# SAMD20_Xplained_Pro_dual_input_power_sup.net
KiCad netlist of a schematic drawn in Altium Designer
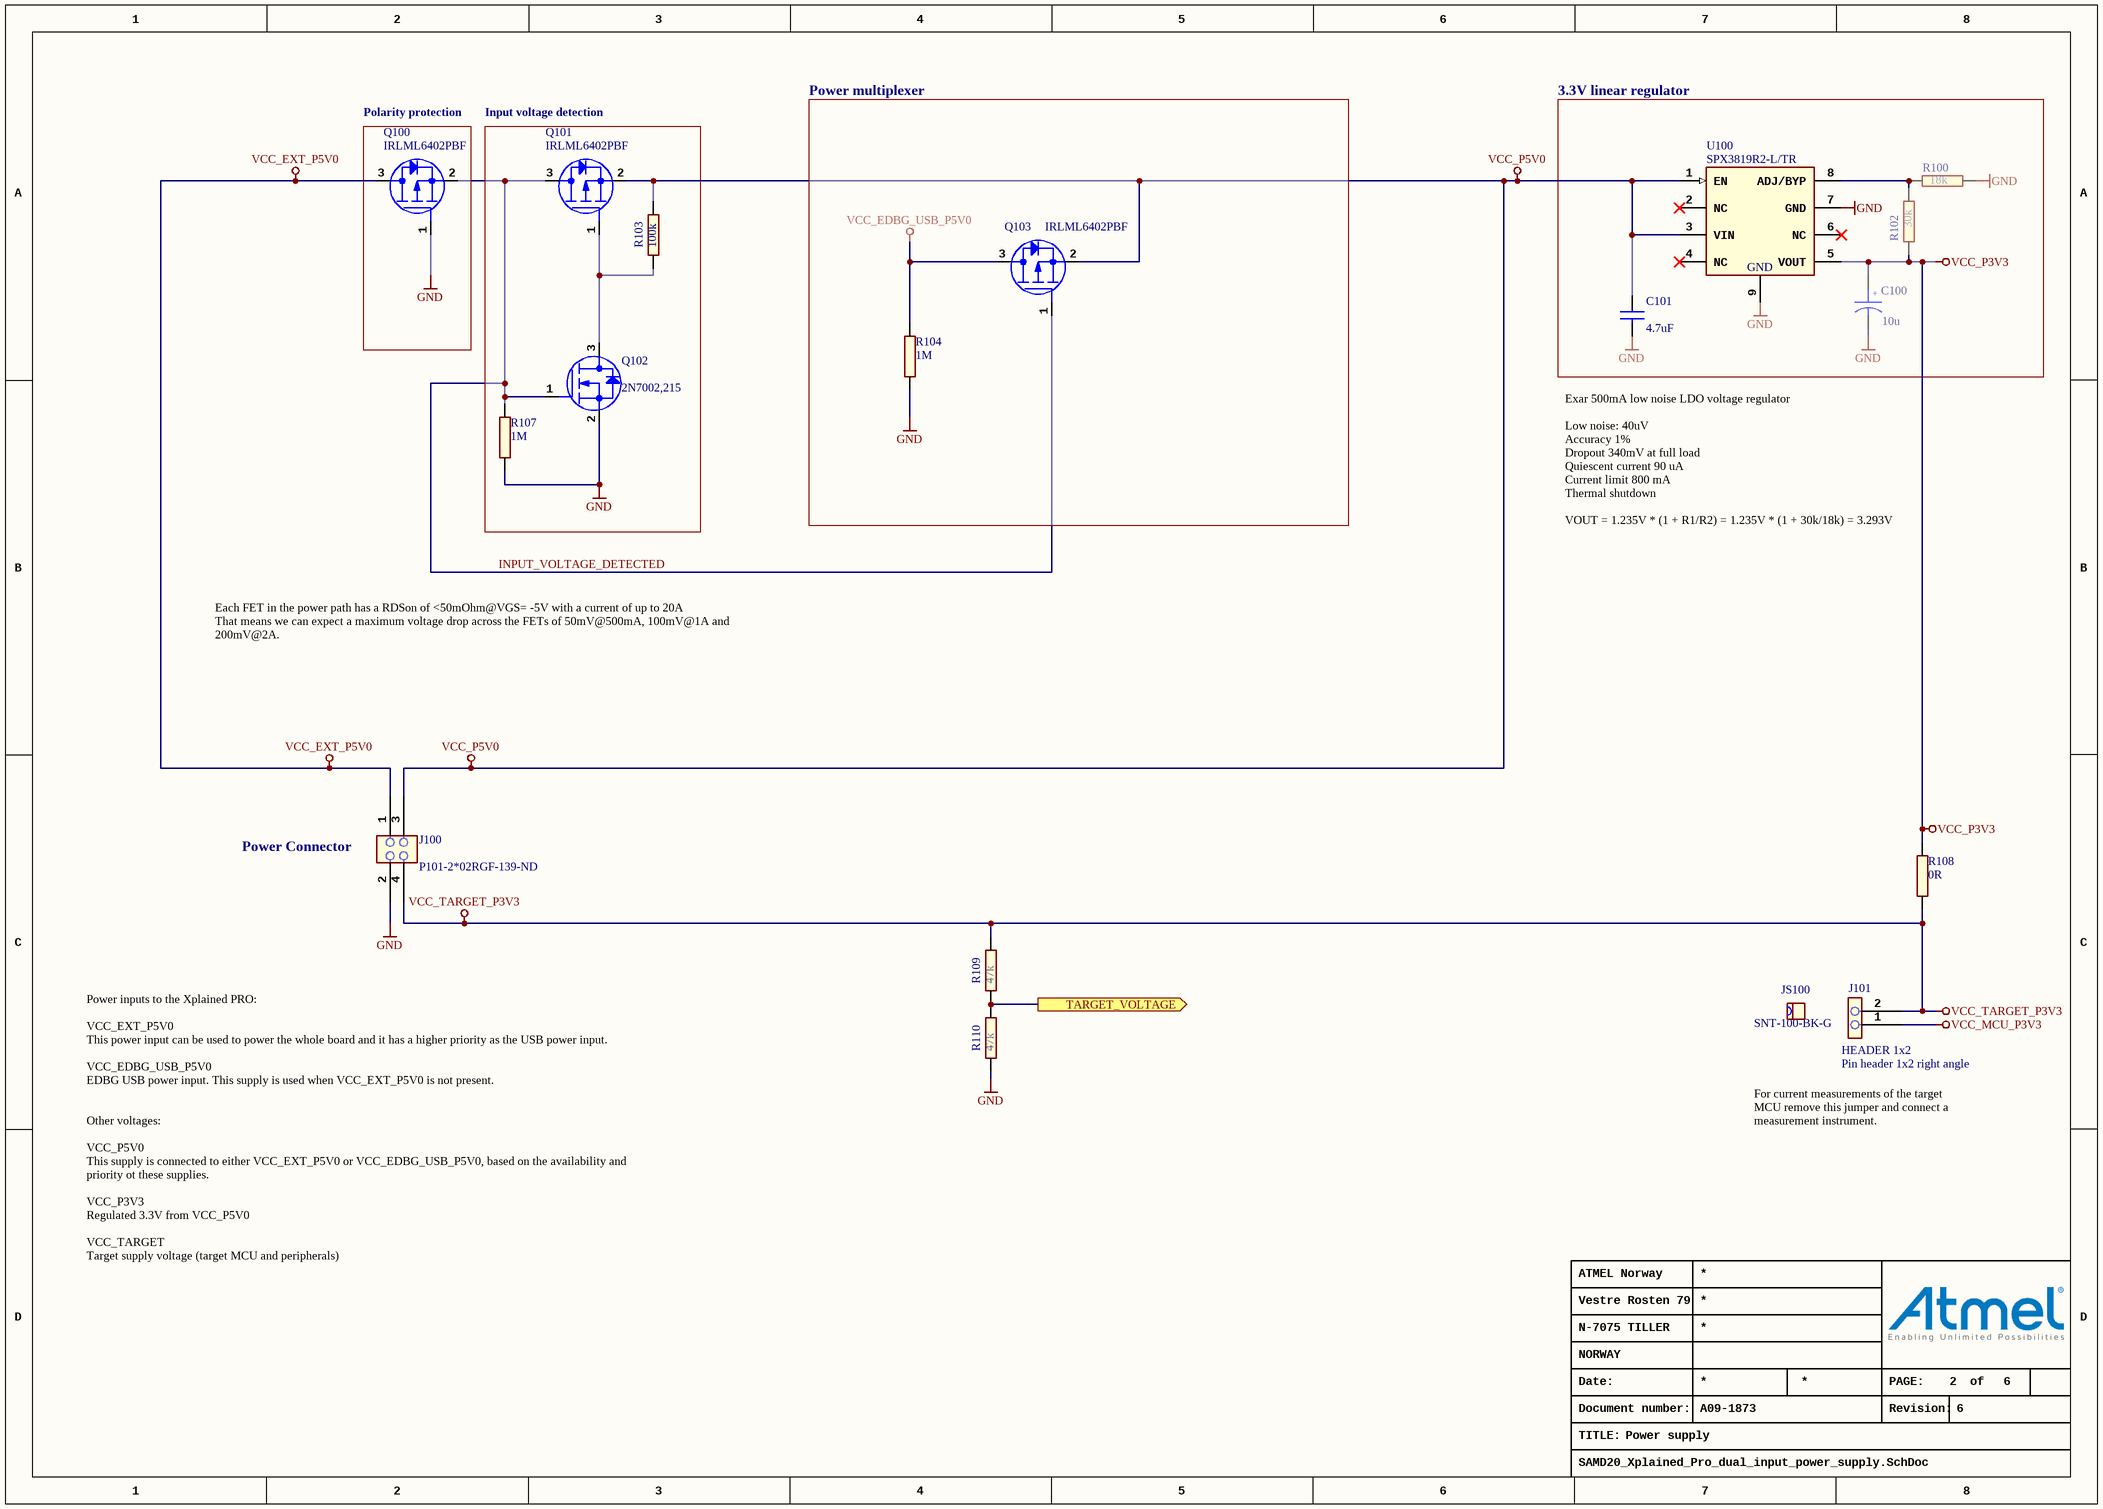
[diagram p0: SAMD20_Xplained_Pro_dual_input_power_supply.SchDoc]

(export (version "E")
  (design (tool "Eeschema 10.0.6"))
  (components
    (comp (ref "C100")
      (value "10u")
      (footprint "AP1-00036")
      (description "SMD tantalum capacitor, ESR = 1.7, 3216-18 (EIA) 1206,")
      (fields (field (name "TOLERANCE") "+-10%") (field (name "MANUFACTURER") "vishay"))
      (libsource (lib "AltiumDbLib") (part "CAP-POL"))
    )
    (comp (ref "C101")
      (value "4.7uF")
      (footprint "AP1-00039")
      (description "Ceramic capacitor, SMD 0603, X5R, 10V, 10% (de31036)")
      (fields (field (name "TOLERANCE") "10%") (field (name "MANUFACTURER") "tdk"))
      (libsource (lib "AltiumDbLib") (part "CAP-NONPOL"))
    )
    (comp (ref "J100")
      (value "P101-2*02RGF-139-ND")
      (footprint "AP8-00628")
      (description "Pin header, 2x2, Right Angle, 2.54mm, THT, Pin In Paste")
      (fields (field (name "Comment") "HEADER 2x2"))
      (libsource (lib "AltiumDbLib") (part "HEADER 2x2"))
    )
    (comp (ref "J101")
      (value "HEADER 1x2")
      (footprint "AP8-00367")
      (description "1x2 pin header, right angle, 2.54 mm pitch, through-hole")
      (fields
        (field (name "ALTIUM_VALUE") "Pin header 1x2 right angle")
        (field (name "MANUFACTURER") "Pro-data International Corp")
        (field (name "MPN") "2213R-2G")
      )
      (libsource (lib "AltiumDbLib") (part "HEADER 1x2"))
    )
    (comp (ref "JS100")
      (value "SNT-100-BK-G")
      (footprint "AP8-00525")
      (description "Jumper cap for 2.54mm pinheader")
      (fields (field (name "MANUFACTURER") "SAMTEC"))
      (libsource (lib "AltiumDbLib") (part "JUMPER_CAP"))
    )
    (comp (ref "Q100")
      (value "IRLML6402PBF")
      (footprint "AP5-00002")
      (description "P-ch. MOSFET. -30V, -3.7A continuous,RDS(ON)=0.05Ohm@VGS=-4,5V, RDS(ON)=0.08Ohm@VGS=-2.5V")
      (fields (field (name "MANUFACTURER") "International Rectifier") (field (name "Comment") "MOSFET_P_GSD"))
      (libsource (lib "AltiumDbLib") (part "MOSFET_P_GSD"))
    )
    (comp (ref "Q101")
      (value "IRLML6402PBF")
      (footprint "AP5-00002")
      (description "P-ch. MOSFET. -30V, -3.7A continuous,RDS(ON)=0.05Ohm@VGS=-4,5V, RDS(ON)=0.08Ohm@VGS=-2.5V")
      (fields (field (name "MANUFACTURER") "International Rectifier") (field (name "Comment") "MOSFET_P_GSD"))
      (libsource (lib "AltiumDbLib") (part "MOSFET_P_GSD"))
    )
    (comp (ref "Q102")
      (value "2N7002,215")
      (footprint "AP5-00002")
      (description "N-Channel MOSFET. 60V, 0.300A continuous, 1.2A Peak. RDS(ON) = 3.8Ohm@VGS=4.5V, VGS(th)<2.5V")
      (fields (field (name "MANUFACTURER") "NXP") (field (name "Comment") "MOSFET_N_GSD"))
      (libsource (lib "AltiumDbLib") (part "MOSFET_N_GSD"))
    )
    (comp (ref "Q103")
      (value "IRLML6402PBF")
      (footprint "AP5-00002")
      (description "P-ch. MOSFET. -30V, -3.7A continuous,RDS(ON)=0.05Ohm@VGS=-4,5V, RDS(ON)=0.08Ohm@VGS=-2.5V")
      (fields (field (name "MANUFACTURER") "International Rectifier") (field (name "Comment") "MOSFET_P_GSD"))
      (libsource (lib "AltiumDbLib") (part "MOSFET_P_GSD"))
    )
    (comp (ref "R100")
      (value "18k")
      (footprint "AP2-00000")
      (description "Thick film resistor, SMD 0402, 1/16W, 1%")
      (fields (field (name "TOLERANCE") "1 %") (field (name "Comment") "R2"))
      (libsource (lib "") (part "R2_3"))
    )
    (comp (ref "R102")
      (value "30k")
      (footprint "AP2-00000")
      (description "Thick film resistor, SMD 0402, 1/16W, 1%")
      (fields (field (name "TOLERANCE") "1 %") (field (name "Comment") "R2"))
      (libsource (lib "") (part "R2_2"))
    )
    (comp (ref "R103")
      (value "100k")
      (footprint "AP2-00000")
      (description "Thick film resistor, SMD 0402, 1/16W, 1%")
      (fields (field (name "TOLERANCE") "1 %") (field (name "Comment") "R2"))
      (libsource (lib "") (part "R2_2"))
    )
    (comp (ref "R104")
      (value "1M")
      (footprint "AP2-00000")
      (description "Thick film resistor, SMD 0402, 1/16W, 1%")
      (fields (field (name "TOLERANCE") "1 %") (field (name "MANUFACTURER") "KOA"))
      (libsource (lib "") (part "R2_2"))
    )
    (comp (ref "R107")
      (value "1M")
      (footprint "AP2-00000")
      (description "Thick film resistor, SMD 0402, 1/16W, 1%")
      (fields (field (name "TOLERANCE") "1 %") (field (name "Comment") "R2"))
      (libsource (lib "") (part "R2_2"))
    )
    (comp (ref "R108")
      (value "0R")
      (footprint "AP2-00000")
      (description "Thick film resistor, SMD 0402, 1/16W, 1%")
      (fields (field (name "TOLERANCE") "1 %") (field (name "Comment") "R2"))
      (libsource (lib "") (part "R2_1"))
    )
    (comp (ref "R109")
      (value "47k")
      (footprint "AP2-00000")
      (description "Thick film resistor, SMD 0402, 1/16W, 1%")
      (fields (field (name "TOLERANCE") "1 %") (field (name "Comment") "R2"))
      (libsource (lib "AltiumDbLib") (part "R2"))
    )
    (comp (ref "R110")
      (value "47k")
      (footprint "AP2-00000")
      (description "Thick film resistor, SMD 0402, 1/16W, 1%")
      (fields (field (name "TOLERANCE") "1 %") (field (name "Comment") "R2"))
      (libsource (lib "AltiumDbLib") (part "R2"))
    )
    (comp (ref "U100")
      (value "SPX3819R2-L/TR")
      (footprint "AP6-00338")
      (description "500mA LDO, ADJ, low noise, 8-DFN package")
      (fields (field (name "TOLERANCE") "±1%") (field (name "MANUFACTURER") "Exar"))
      (libsource (lib "AltiumDbLib") (part "SPX3819R2-L"))
    )
  )
  (nets
    (net (code "1") (name "/INPUT_VOLTAGE_DETECTED") (class "Default")
      (node (ref "Q100") (pin "2") (pinfunction "S_2") (pintype "passive"))
      (node (ref "Q101") (pin "3") (pinfunction "D_3") (pintype "passive"))
      (node (ref "Q102") (pin "1") (pinfunction "G_1") (pintype "passive"))
      (node (ref "Q103") (pin "1") (pinfunction "G_1") (pintype "passive"))
      (node (ref "R107") (pin "2") (pinfunction "2_2") (pintype "passive"))
    )
    (net (code "2") (name "/TARGET_VOLTAGE") (class "Default")
      (node (ref "R109") (pin "1") (pinfunction "1_1") (pintype "passive"))
      (node (ref "R110") (pin "2") (pinfunction "2_2") (pintype "passive"))
    )
    (net (code "3") (name "GND") (class "Default")
      (node (ref "C100") (pin "2") (pinfunction "2_2") (pintype "passive"))
      (node (ref "C101") (pin "2") (pinfunction "2_2") (pintype "passive"))
      (node (ref "J100") (pin "2") (pinfunction "2_2") (pintype "passive"))
      (node (ref "Q100") (pin "1") (pinfunction "G_1") (pintype "passive"))
      (node (ref "Q102") (pin "2") (pinfunction "S_2") (pintype "passive"))
      (node (ref "R100") (pin "2") (pinfunction "2_2") (pintype "passive"))
      (node (ref "R104") (pin "1") (pinfunction "1_1") (pintype "passive"))
      (node (ref "R107") (pin "1") (pinfunction "1_1") (pintype "passive"))
      (node (ref "R110") (pin "1") (pinfunction "1_1") (pintype "passive"))
      (node (ref "U100") (pin "7") (pinfunction "GND_7") (pintype "power_in"))
      (node (ref "U100") (pin "9") (pinfunction "GND_9") (pintype "power_in"))
    )
    (net (code "4") (name "Net-(Q101-G)") (class "Default")
      (node (ref "Q101") (pin "1") (pinfunction "G_1") (pintype "passive"))
      (node (ref "Q102") (pin "3") (pinfunction "D_3") (pintype "passive"))
      (node (ref "R103") (pin "1") (pinfunction "1_1") (pintype "passive"))
    )
    (net (code "5") (name "Net-(U100-ADJ{slash}BYP)") (class "Default")
      (node (ref "R100") (pin "1") (pinfunction "1_1") (pintype "passive"))
      (node (ref "R102") (pin "2") (pinfunction "2_2") (pintype "passive"))
      (node (ref "U100") (pin "8") (pinfunction "ADJ/BYP_8") (pintype "passive"))
    )
    (net (code "6") (name "VCC_EDBG_USB_P5V0") (class "Default")
      (node (ref "Q103") (pin "3") (pinfunction "D_3") (pintype "passive"))
      (node (ref "R104") (pin "2") (pinfunction "2_2") (pintype "passive"))
    )
    (net (code "7") (name "VCC_EXT_P5V0") (class "Default")
      (node (ref "J100") (pin "1") (pinfunction "1_1") (pintype "passive"))
      (node (ref "Q100") (pin "3") (pinfunction "D_3") (pintype "passive"))
    )
    (net (code "8") (name "VCC_MCU_P3V3") (class "Default")
      (node (ref "J101") (pin "1") (pinfunction "1_1") (pintype "passive"))
    )
    (net (code "9") (name "VCC_P3V3") (class "Default")
      (node (ref "C100") (pin "1") (pinfunction "1_1") (pintype "passive"))
      (node (ref "R102") (pin "1") (pinfunction "1_1") (pintype "passive"))
      (node (ref "R108") (pin "1") (pinfunction "1_1") (pintype "passive"))
      (node (ref "U100") (pin "5") (pinfunction "VOUT_5") (pintype "power_in"))
    )
    (net (code "10") (name "VCC_P5V0") (class "Default")
      (node (ref "C101") (pin "1") (pinfunction "1_1") (pintype "passive"))
      (node (ref "J100") (pin "3") (pinfunction "3_3") (pintype "passive"))
      (node (ref "Q101") (pin "2") (pinfunction "S_2") (pintype "passive"))
      (node (ref "Q103") (pin "2") (pinfunction "S_2") (pintype "passive"))
      (node (ref "R103") (pin "2") (pinfunction "2_2") (pintype "passive"))
      (node (ref "U100") (pin "1") (pinfunction "EN_1") (pintype "input"))
      (node (ref "U100") (pin "3") (pinfunction "VIN_3") (pintype "power_in"))
    )
    (net (code "11") (name "VCC_TARGET_P3V3") (class "Default")
      (node (ref "J100") (pin "4") (pinfunction "4_4") (pintype "passive"))
      (node (ref "J101") (pin "2") (pinfunction "2_2") (pintype "passive"))
      (node (ref "R108") (pin "2") (pinfunction "2_2") (pintype "passive"))
      (node (ref "R109") (pin "2") (pinfunction "2_2") (pintype "passive"))
    )
    (net (code "12") (name "unconnected-(U100-NC-Pad2)") (class "Default")
      (node (ref "U100") (pin "2") (pinfunction "NC_2") (pintype "passive+no_connect"))
    )
    (net (code "13") (name "unconnected-(U100-NC-Pad4)") (class "Default")
      (node (ref "U100") (pin "4") (pinfunction "NC_4") (pintype "passive+no_connect"))
    )
    (net (code "14") (name "unconnected-(U100-NC-Pad6)") (class "Default")
      (node (ref "U100") (pin "6") (pinfunction "NC_6") (pintype "passive+no_connect"))
    )
  )
)
